# shield_RN2483A.net
KiCad netlist of a schematic drawn in EAGLE
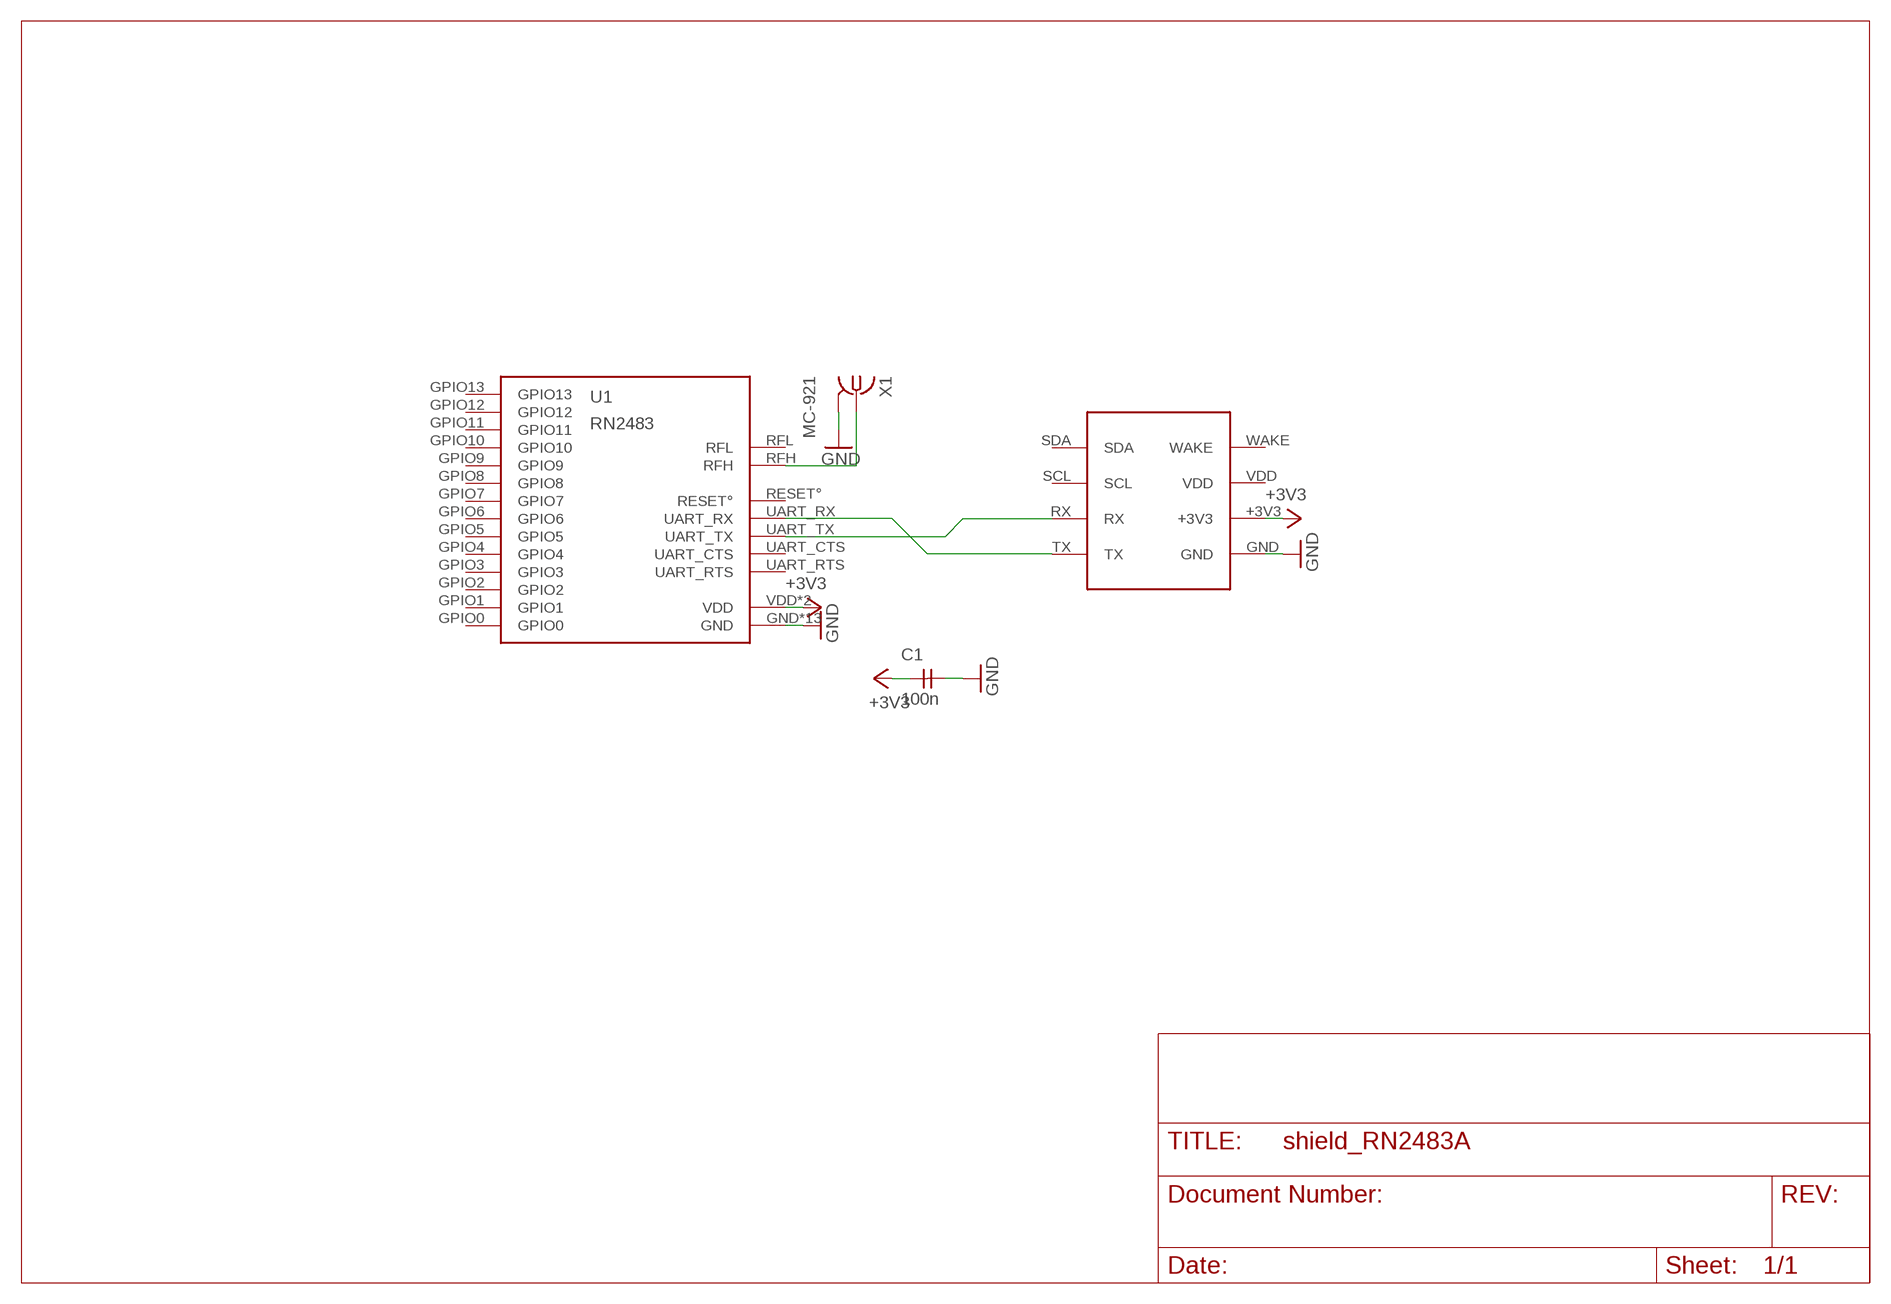
[diagram p0: schematic, sheet 1]

(export (version "E")
  (design (tool "Eeschema 10.0.6"))
  (components
    (comp (ref "C1")
      (value "100n")
      (footprint "eagle-import:SMD_RC_1206")
      (libsource (lib "eagle-import") (part "CSMD_1206"))
    )
    (comp (ref "U$1")
      (value "SHIELD")
      (footprint "eagle-import:SHIELD")
      (libsource (lib "eagle-import") (part "SHIELD"))
    )
    (comp (ref "U1")
      (value "RN2483")
      (footprint "eagle-import:RN2483")
      (libsource (lib "eagle-import") (part "RN2483"))
    )
    (comp (ref "X1")
      (value "MC-921")
      (footprint "eagle-import:MC-921")
      (libsource (lib "eagle-import") (part "MC-921"))
    )
  )
  (nets
    (net (code "1") (name "+3V3") (class "Default")
      (node (ref "C1") (pin "P$1") (pinfunction "1_P$1") (pintype "passive"))
      (node (ref "U$1") (pin "+3V3") (pinfunction "+3V3_+3V3") (pintype "power_in"))
      (node (ref "U1") (pin "VDD") (pinfunction "VDD_VDD") (pintype "bidirectional"))
      (node (ref "U1") (pin "VDD2") (pinfunction "VDD_VDD2") (pintype "bidirectional"))
    )
    (net (code "2") (name "/VDD") (class "Default")
      (node (ref "U$1") (pin "VDD") (pinfunction "VDD_VDD") (pintype "power_in"))
    )
    (net (code "3") (name "GND") (class "Default")
      (node (ref "C1") (pin "P$2") (pinfunction "2_P$2") (pintype "passive"))
      (node (ref "U$1") (pin "GND") (pinfunction "GND_GND") (pintype "power_in"))
      (node (ref "U1") (pin "GND") (pinfunction "GND_GND") (pintype "bidirectional"))
      (node (ref "U1") (pin "GND1") (pinfunction "GND_GND1") (pintype "bidirectional"))
      (node (ref "U1") (pin "GND10") (pinfunction "GND_GND10") (pintype "bidirectional"))
      (node (ref "U1") (pin "GND11") (pinfunction "GND_GND11") (pintype "bidirectional"))
      (node (ref "U1") (pin "GND12") (pinfunction "GND_GND12") (pintype "bidirectional"))
      (node (ref "U1") (pin "GND2") (pinfunction "GND_GND2") (pintype "bidirectional"))
      (node (ref "U1") (pin "GND3") (pinfunction "GND_GND3") (pintype "bidirectional"))
      (node (ref "U1") (pin "GND4") (pinfunction "GND_GND4") (pintype "bidirectional"))
      (node (ref "U1") (pin "GND5") (pinfunction "GND_GND5") (pintype "bidirectional"))
      (node (ref "U1") (pin "GND6") (pinfunction "GND_GND6") (pintype "bidirectional"))
      (node (ref "U1") (pin "GND7") (pinfunction "GND_GND7") (pintype "bidirectional"))
      (node (ref "U1") (pin "GND8") (pinfunction "GND_GND8") (pintype "bidirectional"))
      (node (ref "U1") (pin "GND9") (pinfunction "GND_GND9") (pintype "bidirectional"))
      (node (ref "X1") (pin "2@1") (pinfunction "GND_2@1") (pintype "passive"))
      (node (ref "X1") (pin "2@2") (pinfunction "GND_2@2") (pintype "passive"))
    )
    (net (code "4") (name "Net-(U$1-PadRX)") (class "Default")
      (node (ref "U$1") (pin "RX") (pinfunction "RX_RX") (pintype "input"))
      (node (ref "U1") (pin "UART_TX") (pinfunction "UART_TX_UART_TX") (pintype "bidirectional"))
    )
    (net (code "5") (name "Net-(U$1-PadTX)") (class "Default")
      (node (ref "U$1") (pin "TX") (pinfunction "TX_TX") (pintype "output"))
      (node (ref "U1") (pin "UART_RX") (pinfunction "UART_RX_UART_RX") (pintype "bidirectional"))
    )
    (net (code "6") (name "Net-(U1-PadRFH)") (class "Default")
      (node (ref "U1") (pin "RFH") (pinfunction "RFH_RFH") (pintype "bidirectional"))
      (node (ref "X1") (pin "1") (pinfunction "1_1") (pintype "passive"))
    )
    (net (code "7") (name "unconnected-(U$1-PadSCL)") (class "Default")
      (node (ref "U$1") (pin "SCL") (pinfunction "SCL_SCL") (pintype "output"))
    )
    (net (code "8") (name "unconnected-(U$1-PadSDA)") (class "Default")
      (node (ref "U$1") (pin "SDA") (pinfunction "SDA_SDA") (pintype "bidirectional"))
    )
    (net (code "9") (name "unconnected-(U$1-PadWAKE)") (class "Default")
      (node (ref "U$1") (pin "WAKE") (pinfunction "WAKE_WAKE") (pintype "output"))
    )
    (net (code "10") (name "unconnected-(U1-PadGPIO0)") (class "Default")
      (node (ref "U1") (pin "GPIO0") (pinfunction "GPIO0_GPIO0") (pintype "bidirectional"))
    )
    (net (code "11") (name "unconnected-(U1-PadGPIO1)") (class "Default")
      (node (ref "U1") (pin "GPIO1") (pinfunction "GPIO1_GPIO1") (pintype "bidirectional"))
    )
    (net (code "12") (name "unconnected-(U1-PadGPIO2)") (class "Default")
      (node (ref "U1") (pin "GPIO2") (pinfunction "GPIO2_GPIO2") (pintype "bidirectional"))
    )
    (net (code "13") (name "unconnected-(U1-PadGPIO3)") (class "Default")
      (node (ref "U1") (pin "GPIO3") (pinfunction "GPIO3_GPIO3") (pintype "bidirectional"))
    )
    (net (code "14") (name "unconnected-(U1-PadGPIO4)") (class "Default")
      (node (ref "U1") (pin "GPIO4") (pinfunction "GPIO4_GPIO4") (pintype "bidirectional"))
    )
    (net (code "15") (name "unconnected-(U1-PadGPIO5)") (class "Default")
      (node (ref "U1") (pin "GPIO5") (pinfunction "GPIO5_GPIO5") (pintype "bidirectional"))
    )
    (net (code "16") (name "unconnected-(U1-PadGPIO6)") (class "Default")
      (node (ref "U1") (pin "GPIO6") (pinfunction "GPIO6_GPIO6") (pintype "bidirectional"))
    )
    (net (code "17") (name "unconnected-(U1-PadGPIO7)") (class "Default")
      (node (ref "U1") (pin "GPIO7") (pinfunction "GPIO7_GPIO7") (pintype "bidirectional"))
    )
    (net (code "18") (name "unconnected-(U1-PadGPIO8)") (class "Default")
      (node (ref "U1") (pin "GPIO8") (pinfunction "GPIO8_GPIO8") (pintype "bidirectional"))
    )
    (net (code "19") (name "unconnected-(U1-PadGPIO9)") (class "Default")
      (node (ref "U1") (pin "GPIO9") (pinfunction "GPIO9_GPIO9") (pintype "bidirectional"))
    )
    (net (code "20") (name "unconnected-(U1-PadGPIO10)") (class "Default")
      (node (ref "U1") (pin "GPIO10") (pinfunction "GPIO10_GPIO10") (pintype "bidirectional"))
    )
    (net (code "21") (name "unconnected-(U1-PadGPIO11)") (class "Default")
      (node (ref "U1") (pin "GPIO11") (pinfunction "GPIO11_GPIO11") (pintype "bidirectional"))
    )
    (net (code "22") (name "unconnected-(U1-PadGPIO12)") (class "Default")
      (node (ref "U1") (pin "GPIO12") (pinfunction "GPIO12_GPIO12") (pintype "bidirectional"))
    )
    (net (code "23") (name "unconnected-(U1-PadGPIO13)") (class "Default")
      (node (ref "U1") (pin "GPIO13") (pinfunction "GPIO13_GPIO13") (pintype "bidirectional"))
    )
    (net (code "24") (name "unconnected-(U1-PadRESET°)") (class "Default")
      (node (ref "U1") (pin "RESET°") (pinfunction "RESET°_RESET°") (pintype "bidirectional"))
    )
    (net (code "25") (name "unconnected-(U1-PadRFL)") (class "Default")
      (node (ref "U1") (pin "RFL") (pinfunction "RFL_RFL") (pintype "bidirectional"))
    )
    (net (code "26") (name "unconnected-(U1-PadUART_CTS)") (class "Default")
      (node (ref "U1") (pin "UART_CTS") (pinfunction "UART_CTS_UART_CTS") (pintype "bidirectional"))
    )
    (net (code "27") (name "unconnected-(U1-PadUART_RTS)") (class "Default")
      (node (ref "U1") (pin "UART_RTS") (pinfunction "UART_RTS_UART_RTS") (pintype "bidirectional"))
    )
  )
)
